# karmanDB_accel.net
KiCad netlist of a schematic drawn in Altium Designer
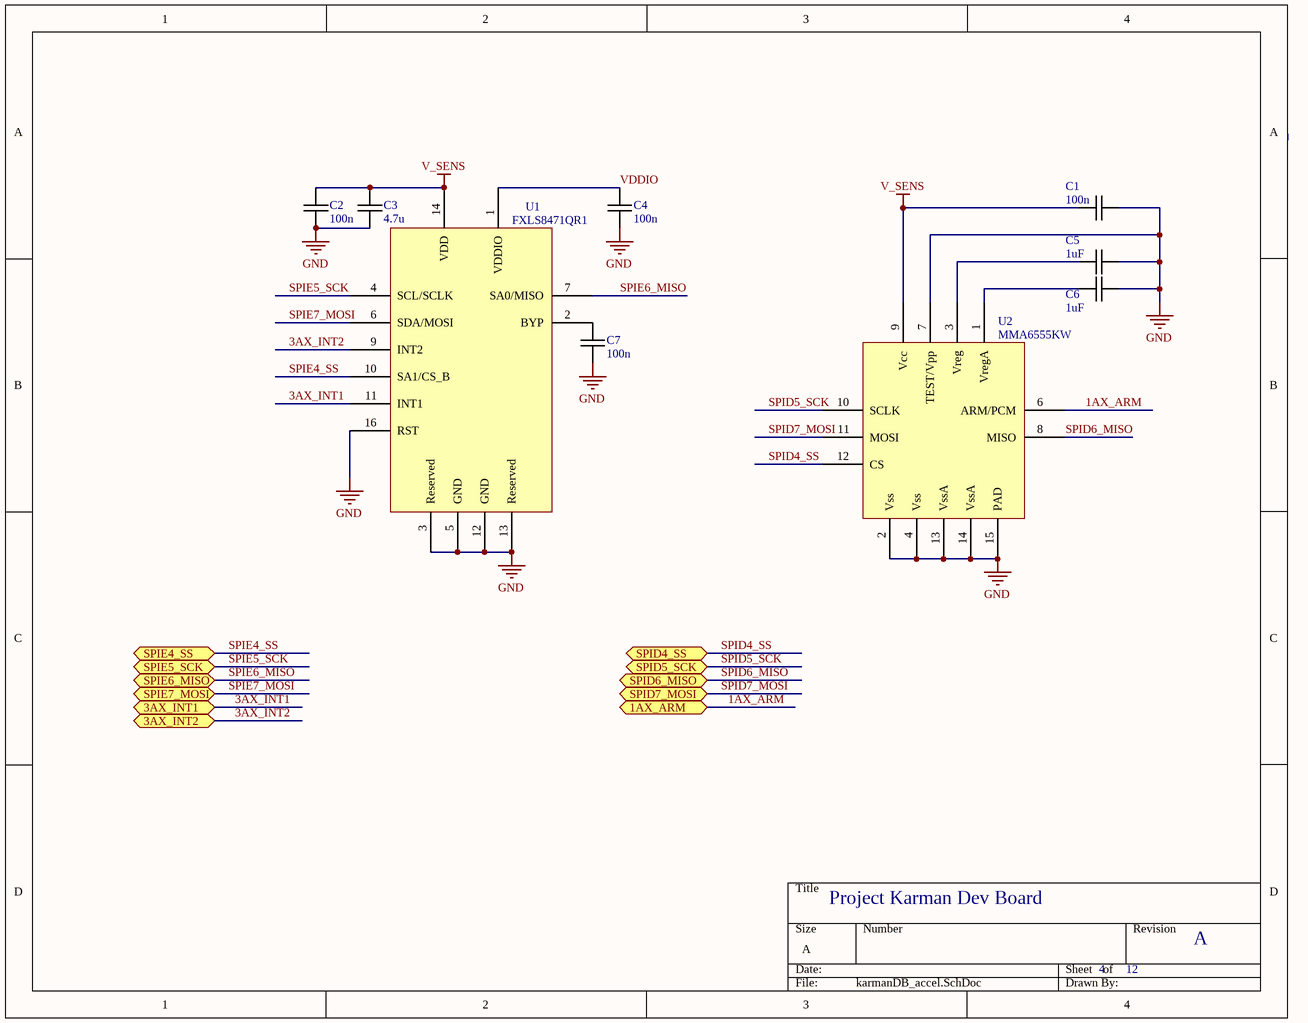
[diagram p0: karmanDB_accel.SchDoc]

(export (version "E")
  (design (tool "Eeschema 10.0.6"))
  (components
    (comp (ref "C1")
      (value "100n")
      (footprint "MURATA_GRM_0603")
      (description "CAP CER 0.1UF 16V 10% X7R 0603")
      (fields
        (field (name "MANUFACTURER") "Murata Electronics North America")
        (field (name "MANUFACTURER PART NUMBER") "GRM188R71C104KA01D")
      )
      (libsource (lib "project_symbols") (part "CAP_MURATA_GRM188R71C104KA01D"))
    )
    (comp (ref "C2")
      (value "100n")
      (footprint "MURATA_GRM_0603")
      (description "CAP CER 0.1UF 16V 10% X7R 0603")
      (fields
        (field (name "MANUFACTURER") "Murata Electronics North America")
        (field (name "MANUFACTURER PART NUMBER") "GRM188R71C104KA01D")
      )
      (libsource (lib "project_symbols") (part "CAP_MURATA_GRM188R71C104KA01D"))
    )
    (comp (ref "C3")
      (value "4.7u")
      (footprint "MURATA_GRM_0603")
      (description "CAP CER 4.7UF 16V 20% X5R 0603")
      (fields
        (field (name "MANUFACTURER") "Murata Electronics North America")
        (field (name "MANUFACTURER PART NUMBER") "GRM188R61C475MAAJD")
      )
      (libsource (lib "project_symbols") (part "CAP_MURATA_GRM188R61C475MAAJD"))
    )
    (comp (ref "C4")
      (value "100n")
      (footprint "MURATA_GRM_0603")
      (description "CAP CER 0.1UF 16V 10% X7R 0603")
      (fields
        (field (name "MANUFACTURER") "Murata Electronics North America")
        (field (name "MANUFACTURER PART NUMBER") "GRM188R71C104KA01D")
      )
      (libsource (lib "project_symbols") (part "CAP_MURATA_GRM188R71C104KA01D"))
    )
    (comp (ref "C5")
      (value "1uF")
      (footprint "MURATA_GRM_0402")
      (description "CAP CER 1uF 10volts X5R 10% 0402")
      (fields
        (field (name "MANUFACTURER") "Murata Electronics")
        (field (name "MANUFACTURER PART NUMBER") "GRM155R61A105KE15D")
      )
      (libsource (lib "project_symbols") (part "CAP_MURATA_GRM155R61A105KE15D"))
    )
    (comp (ref "C6")
      (value "1uF")
      (footprint "MURATA_GRM_0402")
      (description "CAP CER 1uF 10volts X5R 10% 0402")
      (fields
        (field (name "MANUFACTURER") "Murata Electronics")
        (field (name "MANUFACTURER PART NUMBER") "GRM155R61A105KE15D")
      )
      (libsource (lib "project_symbols") (part "CAP_MURATA_GRM155R61A105KE15D"))
    )
    (comp (ref "C7")
      (value "100n")
      (footprint "MURATA_GRM_0603")
      (description "CAP CER 0.1UF 16V 10% X7R 0603")
      (fields
        (field (name "MANUFACTURER") "Murata Electronics North America")
        (field (name "MANUFACTURER PART NUMBER") "GRM188R71C104KA01D")
      )
      (libsource (lib "project_symbols") (part "CAP_MURATA_GRM188R71C104KA01D"))
    )
    (comp (ref "U1")
      (value "FXLS8471QR1")
      (footprint "3 FXLS8471QR1")
      (description "ACCELEROMETER LOW G 3-AXIS DFN")
      (fields (field (name "MANUFACTURER") "Freescale Semiconductor"))
      (libsource (lib "karman_pcb") (part "FXLS8471QR1"))
    )
    (comp (ref "U2")
      (value "MMA6555KW")
      (footprint "6 MMA6555KW")
      (description "Accelerometers X-AXIS 100G")
      (fields (field (name "MANUFACTURER") "Freescale Semiconductor"))
      (libsource (lib "karman_pcb") (part "MMA6555KW"))
    )
  )
  (nets
    (net (code "1") (name "/1AX_ARM") (class "Default")
      (node (ref "U2") (pin "6") (pinfunction "ARM/PCM_6") (pintype "passive"))
    )
    (net (code "2") (name "/3AX_INT1") (class "Default")
      (node (ref "U1") (pin "11") (pinfunction "INT1_11") (pintype "passive"))
    )
    (net (code "3") (name "/3AX_INT2") (class "Default")
      (node (ref "U1") (pin "9") (pinfunction "INT2_9") (pintype "passive"))
    )
    (net (code "4") (name "/SPID4_SS") (class "Default")
      (node (ref "U2") (pin "12") (pinfunction "CS_12") (pintype "passive"))
    )
    (net (code "5") (name "/SPID5_SCK") (class "Default")
      (node (ref "U2") (pin "10") (pinfunction "SCLK_10") (pintype "passive"))
    )
    (net (code "6") (name "/SPID6_MISO") (class "Default")
      (node (ref "U2") (pin "8") (pinfunction "MISO_8") (pintype "passive"))
    )
    (net (code "7") (name "/SPID7_MOSI") (class "Default")
      (node (ref "U2") (pin "11") (pinfunction "MOSI_11") (pintype "passive"))
    )
    (net (code "8") (name "/SPIE4_SS") (class "Default")
      (node (ref "U1") (pin "10") (pinfunction "SA1/CS_B_10") (pintype "passive"))
    )
    (net (code "9") (name "/SPIE5_SCK") (class "Default")
      (node (ref "U1") (pin "4") (pinfunction "SCL/SCLK_4") (pintype "passive"))
    )
    (net (code "10") (name "/SPIE6_MISO") (class "Default")
      (node (ref "U1") (pin "7") (pinfunction "SA0/MISO_7") (pintype "passive"))
    )
    (net (code "11") (name "/SPIE7_MOSI") (class "Default")
      (node (ref "U1") (pin "6") (pinfunction "SDA/MOSI_6") (pintype "passive"))
    )
    (net (code "12") (name "/VDDIO") (class "Default")
      (node (ref "C4") (pin "1") (pintype "passive"))
      (node (ref "U1") (pin "1") (pinfunction "VDDIO_1") (pintype "passive"))
    )
    (net (code "13") (name "GND") (class "Default")
      (node (ref "C1") (pin "2") (pintype "passive"))
      (node (ref "C2") (pin "2") (pintype "passive"))
      (node (ref "C3") (pin "2") (pintype "passive"))
      (node (ref "C4") (pin "2") (pintype "passive"))
      (node (ref "C5") (pin "1") (pintype "passive"))
      (node (ref "C6") (pin "1") (pintype "passive"))
      (node (ref "C7") (pin "2") (pintype "passive"))
      (node (ref "U1") (pin "12") (pinfunction "GND_12") (pintype "passive"))
      (node (ref "U1") (pin "13") (pinfunction "Reserved_13") (pintype "passive"))
      (node (ref "U1") (pin "16") (pinfunction "RST_16") (pintype "passive"))
      (node (ref "U1") (pin "3") (pinfunction "Reserved_3") (pintype "passive"))
      (node (ref "U1") (pin "5") (pinfunction "GND_5") (pintype "passive"))
      (node (ref "U2") (pin "13") (pinfunction "VssA_13") (pintype "passive"))
      (node (ref "U2") (pin "14") (pinfunction "VssA_14") (pintype "passive"))
      (node (ref "U2") (pin "15") (pinfunction "PAD_15") (pintype "passive"))
      (node (ref "U2") (pin "2") (pinfunction "Vss_2") (pintype "passive"))
      (node (ref "U2") (pin "4") (pinfunction "Vss_4") (pintype "passive"))
      (node (ref "U2") (pin "7") (pinfunction "TEST/Vpp_7") (pintype "passive"))
    )
    (net (code "14") (name "Net-(U1-BYP)") (class "Default")
      (node (ref "C7") (pin "1") (pintype "passive"))
      (node (ref "U1") (pin "2") (pinfunction "BYP_2") (pintype "passive"))
    )
    (net (code "15") (name "Net-(U2-Vreg)") (class "Default")
      (node (ref "C5") (pin "2") (pintype "passive"))
      (node (ref "U2") (pin "3") (pinfunction "Vreg_3") (pintype "passive"))
    )
    (net (code "16") (name "Net-(U2-VregA)") (class "Default")
      (node (ref "C6") (pin "2") (pintype "passive"))
      (node (ref "U2") (pin "1") (pinfunction "VregA_1") (pintype "passive"))
    )
    (net (code "17") (name "V_SENS") (class "Default")
      (node (ref "C1") (pin "1") (pintype "passive"))
      (node (ref "C2") (pin "1") (pintype "passive"))
      (node (ref "C3") (pin "1") (pintype "passive"))
      (node (ref "U1") (pin "14") (pinfunction "VDD_14") (pintype "passive"))
      (node (ref "U2") (pin "9") (pinfunction "Vcc_9") (pintype "passive"))
    )
    (net (code "18") (name "unconnected-(U1-N{slash}C-Pad8)") (class "Default")
      (node (ref "U1") (pin "8") (pinfunction "N/C_8") (pintype "passive"))
    )
    (net (code "19") (name "unconnected-(U1-N{slash}C-Pad15)") (class "Default")
      (node (ref "U1") (pin "15") (pinfunction "N/C_15") (pintype "passive"))
    )
  )
)
